# Adafruit_MatrixPortal_M4.net
KiCad netlist of a schematic drawn in EAGLE
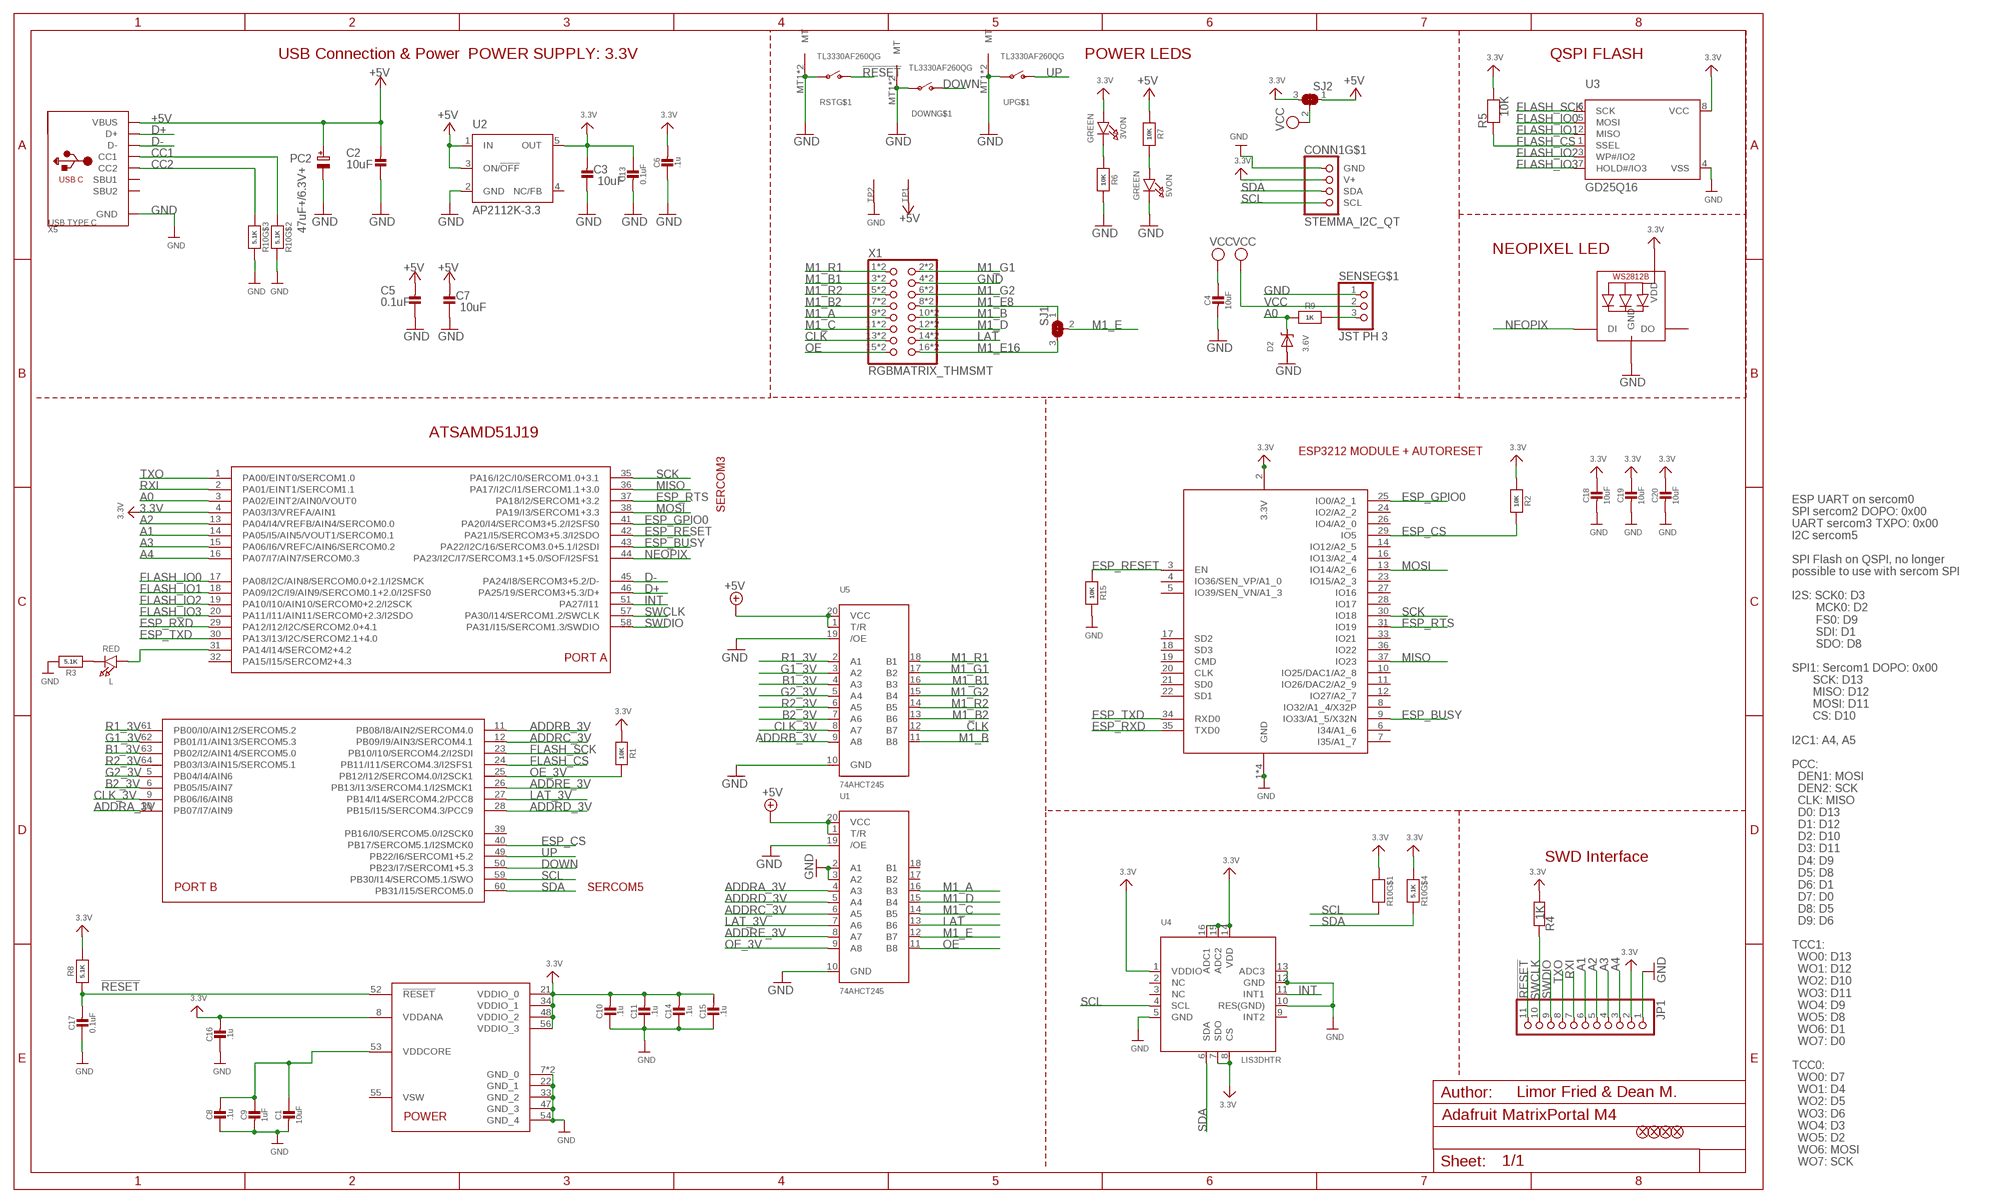
[diagram p0: schematic, sheet 1]

(export (version "E")
  (design (tool "Eeschema 10.0.6"))
  (components
    (comp (ref "3VON")
      (value "GREEN")
      (footprint "eagle-import:CHIPLED_0805_NOOUTLINE")
      (libsource (lib "eagle-import") (part "LED0805_NOOUTLINE"))
    )
    (comp (ref "5VON")
      (value "GREEN")
      (footprint "eagle-import:CHIPLED_0805_NOOUTLINE")
      (libsource (lib "eagle-import") (part "LED0805_NOOUTLINE"))
    )
    (comp (ref "C1")
      (value "10uF")
      (footprint "eagle-import:0805-NO")
      (libsource (lib "eagle-import") (part "CAP_CERAMIC0805-NOOUTLINE"))
    )
    (comp (ref "C2")
      (value "10uF")
      (footprint "eagle-import:0805-NO")
      (libsource (lib "eagle-import") (part "CAP_CERAMIC0805-NOOUTLINE"))
    )
    (comp (ref "C3")
      (value "10uF")
      (footprint "eagle-import:0805-NO")
      (libsource (lib "eagle-import") (part "CAP_CERAMIC0805-NOOUTLINE"))
    )
    (comp (ref "C4")
      (value "10uF")
      (footprint "eagle-import:0805-NO")
      (libsource (lib "eagle-import") (part "CAP_CERAMIC0805-NOOUTLINE"))
    )
    (comp (ref "C5")
      (value "0.1uF")
      (footprint "eagle-import:0603-NO")
      (libsource (lib "eagle-import") (part "CAP_CERAMIC0603_NO"))
    )
    (comp (ref "C6")
      (value ".1u")
      (footprint "eagle-import:0603-NO")
      (libsource (lib "eagle-import") (part "CAP_CERAMIC0603_NO"))
    )
    (comp (ref "C7")
      (value "10uF")
      (footprint "eagle-import:0805-NO")
      (libsource (lib "eagle-import") (part "CAP_CERAMIC0805-NOOUTLINE"))
    )
    (comp (ref "C8")
      (value ".1u")
      (footprint "eagle-import:0603-NO")
      (libsource (lib "eagle-import") (part "CAP_CERAMIC0603_NO"))
    )
    (comp (ref "C9")
      (value "1uF")
      (footprint "eagle-import:0603-NO")
      (libsource (lib "eagle-import") (part "CAP_CERAMIC0603_NO"))
    )
    (comp (ref "C10")
      (value ".1u")
      (footprint "eagle-import:0603-NO")
      (libsource (lib "eagle-import") (part "CAP_CERAMIC0603_NO"))
    )
    (comp (ref "C11")
      (value ".1u")
      (footprint "eagle-import:0603-NO")
      (libsource (lib "eagle-import") (part "CAP_CERAMIC0603_NO"))
    )
    (comp (ref "C13")
      (value "0.1uF")
      (footprint "eagle-import:0603-NO")
      (libsource (lib "eagle-import") (part "CAP_CERAMIC0603_NO"))
    )
    (comp (ref "C14")
      (value ".1u")
      (footprint "eagle-import:0603-NO")
      (libsource (lib "eagle-import") (part "CAP_CERAMIC0603_NO"))
    )
    (comp (ref "C15")
      (value ".1u")
      (footprint "eagle-import:0603-NO")
      (libsource (lib "eagle-import") (part "CAP_CERAMIC0603_NO"))
    )
    (comp (ref "C16")
      (value ".1u")
      (footprint "eagle-import:0603-NO")
      (libsource (lib "eagle-import") (part "CAP_CERAMIC0603_NO"))
    )
    (comp (ref "C17")
      (value "0.1uF")
      (footprint "eagle-import:0603-NO")
      (libsource (lib "eagle-import") (part "CAP_CERAMIC0603_NO"))
    )
    (comp (ref "C18")
      (value "10uF")
      (footprint "eagle-import:0805-NO")
      (libsource (lib "eagle-import") (part "CAP_CERAMIC0805-NOOUTLINE"))
    )
    (comp (ref "C19")
      (value "10uF")
      (footprint "eagle-import:0805-NO")
      (libsource (lib "eagle-import") (part "CAP_CERAMIC0805-NOOUTLINE"))
    )
    (comp (ref "C20")
      (value "10uF")
      (footprint "eagle-import:0805-NO")
      (libsource (lib "eagle-import") (part "CAP_CERAMIC0805-NOOUTLINE"))
    )
    (comp (ref "CONN1")
      (value "STEMMA_I2C_QT")
      (footprint "eagle-import:JST_SH4")
      (libsource (lib "eagle-import") (part "STEMMA_I2C_QT"))
    )
    (comp (ref "D2")
      (value "3.6V")
      (footprint "eagle-import:SOD-323")
      (libsource (lib "eagle-import") (part "DIODE-ZENERSOD323"))
    )
    (comp (ref "DOWN")
      (value "TL3330AF260QG")
      (footprint "eagle-import:SPST_TACTILE_RA")
      (libsource (lib "eagle-import") (part "SWITCH_SPST_TACT_RA"))
    )
    (comp (ref "FID1")
      (value "FIDUCIAL_1MM")
      (footprint "eagle-import:FIDUCIAL_1MM")
      (libsource (lib "eagle-import") (part "FIDUCIAL_1MM"))
    )
    (comp (ref "FID2")
      (value "FIDUCIAL_1MM")
      (footprint "eagle-import:FIDUCIAL_1MM")
      (libsource (lib "eagle-import") (part "FIDUCIAL_1MM"))
    )
    (comp (ref "FID3")
      (value "FIDUCIAL_1MM")
      (footprint "eagle-import:FIDUCIAL_1MM")
      (libsource (lib "eagle-import") (part "FIDUCIAL_1MM"))
    )
    (comp (ref "FID4")
      (value "FIDUCIAL_1MM")
      (footprint "eagle-import:FIDUCIAL_1MM")
      (libsource (lib "eagle-import") (part "FIDUCIAL_1MM"))
    )
    (comp (ref "JP1")
      (value "HEADER-1X11")
      (footprint "eagle-import:1X11_ROUND")
      (libsource (lib "eagle-import") (part "HEADER-1X11"))
    )
    (comp (ref "L")
      (value "RED")
      (footprint "eagle-import:CHIPLED_0603_NOOUTLINE")
      (libsource (lib "eagle-import") (part "LED0603_NOOUTLINE"))
    )
    (comp (ref "LED1")
      (value "WS2812B3535")
      (footprint "eagle-import:LED3535")
      (libsource (lib "eagle-import") (part "WS2812B3535"))
    )
    (comp (ref "PC2")
      (value "47uF+/6.3V+")
      (footprint "eagle-import:PANASONIC_D")
      (libsource (lib "eagle-import") (part "CAP_ELECTROLYTICPANASONIC_D"))
    )
    (comp (ref "R1")
      (value "10K")
      (footprint "eagle-import:0603-NO")
      (libsource (lib "eagle-import") (part "RESISTOR_0603_NOOUT"))
    )
    (comp (ref "R2")
      (value "10K")
      (footprint "eagle-import:0603-NO")
      (libsource (lib "eagle-import") (part "RESISTOR_0603_NOOUT"))
    )
    (comp (ref "R3")
      (value "5.1K")
      (footprint "eagle-import:0603-NO")
      (libsource (lib "eagle-import") (part "RESISTOR_0603_NOOUT"))
    )
    (comp (ref "R4")
      (value "1K")
      (footprint "eagle-import:0603-NO")
      (libsource (lib "eagle-import") (part "RESISTOR_0603_NOOUT"))
    )
    (comp (ref "R5")
      (value "10K")
      (footprint "eagle-import:0603-NO")
      (libsource (lib "eagle-import") (part "RESISTOR_0603_NOOUT"))
    )
    (comp (ref "R6")
      (value "10K")
      (footprint "eagle-import:0603-NO")
      (libsource (lib "eagle-import") (part "RESISTOR_0603_NOOUT"))
    )
    (comp (ref "R7")
      (value "10K")
      (footprint "eagle-import:0603-NO")
      (libsource (lib "eagle-import") (part "RESISTOR_0603_NOOUT"))
    )
    (comp (ref "R8")
      (value "5.1K")
      (footprint "eagle-import:0603-NO")
      (libsource (lib "eagle-import") (part "RESISTOR_0603_NOOUT"))
    )
    (comp (ref "R9")
      (value "1K")
      (footprint "eagle-import:0603-NO")
      (libsource (lib "eagle-import") (part "RESISTOR_0603_NOOUT"))
    )
    (comp (ref "R10")
      (value "5.1K")
      (footprint "eagle-import:RESPACK_4X0603")
      (libsource (lib "eagle-import") (part "RESISTOR_4PACK"))
    )
    (comp (ref "R15")
      (value "10K")
      (footprint "eagle-import:0603-NO")
      (libsource (lib "eagle-import") (part "RESISTOR_0603_NOOUT"))
    )
    (comp (ref "RST")
      (value "TL3330AF260QG")
      (footprint "eagle-import:SPST_TACTILE_RA")
      (libsource (lib "eagle-import") (part "SWITCH_SPST_TACT_RA"))
    )
    (comp (ref "SENSE")
      (value "JST PH 3")
      (footprint "eagle-import:JSTPH3")
      (libsource (lib "eagle-import") (part "CON_JST_PH_3PIN"))
    )
    (comp (ref "SJ1")
      (value "SOLDERJUMPER_2WAY")
      (footprint "eagle-import:SOLDERJUMPER_2WAY_OPEN_NOPASTE")
      (libsource (lib "eagle-import") (part "SOLDERJUMPER_2WAY"))
    )
    (comp (ref "SJ2")
      (value "SOLDERJUMPER_2WAY")
      (footprint "eagle-import:SOLDERJUMPER_2WAY_OPEN_NOPASTE")
      (libsource (lib "eagle-import") (part "SOLDERJUMPER_2WAY"))
    )
    (comp (ref "TP1")
      (value "SEWTAP_SMTNUTM3")
      (footprint "eagle-import:SMT_NUT_3MM")
      (libsource (lib "eagle-import") (part "SEWTAP_SMTNUTM3"))
    )
    (comp (ref "TP2")
      (value "SEWTAP_SMTNUTM3")
      (footprint "eagle-import:SMT_NUT_3MM")
      (libsource (lib "eagle-import") (part "SEWTAP_SMTNUTM3"))
    )
    (comp (ref "U$1")
      (value "ATSAMD51J19")
      (footprint "eagle-import:PQFN64-1")
      (libsource (lib "eagle-import") (part "ATSAMD51J"))
    )
    (comp (ref "U1")
      (value "74AHCT245")
      (footprint "eagle-import:TSSOP20")
      (libsource (lib "eagle-import") (part "74LCX245"))
    )
    (comp (ref "U2")
      (value "AP2112K-3.3")
      (footprint "eagle-import:SOT23-DBV")
      (libsource (lib "eagle-import") (part "LP2985-XXDBVR33"))
    )
    (comp (ref "U3")
      (value "GD25Q16")
      (footprint "eagle-import:SOIC8_208MIL")
      (libsource (lib "eagle-import") (part "SPIFLASH_8PIN208MIL"))
    )
    (comp (ref "U4")
      (value "LIS3DHTR")
      (footprint "eagle-import:LGA16_3X3MM")
      (libsource (lib "eagle-import") (part "ACCEL_LIS3DHTR"))
    )
    (comp (ref "U5")
      (value "74AHCT245")
      (footprint "eagle-import:TSSOP20")
      (libsource (lib "eagle-import") (part "74LCX245"))
    )
    (comp (ref "UP")
      (value "TL3330AF260QG")
      (footprint "eagle-import:SPST_TACTILE_RA")
      (libsource (lib "eagle-import") (part "SWITCH_SPST_TACT_RA"))
    )
    (comp (ref "X1")
      (value "RGBMATRIX_THMSMT")
      (footprint "eagle-import:2X08_SMTTHM_RGBMATRIX")
      (libsource (lib "eagle-import") (part "RGBMATRIX_THMSMT"))
    )
    (comp (ref "X5")
      (value "USB TYPE C")
      (footprint "eagle-import:USB_C_CUSB31-CFM2AX-01-X")
      (libsource (lib "eagle-import") (part "USB_C"))
    )
    (comp (ref "X6")
      (value "ESP32_WROOM32")
      (footprint "eagle-import:WROOM32")
      (libsource (lib "eagle-import") (part "ESP32_WROOM32"))
    )
  )
  (nets
    (net (code "1") (name "+5V") (class "Default")
      (node (ref "C2") (pin "2") (pinfunction "2_2") (pintype "passive"))
      (node (ref "C5") (pin "2") (pinfunction "2_2") (pintype "passive"))
      (node (ref "C7") (pin "2") (pinfunction "2_2") (pintype "passive"))
      (node (ref "PC2") (pin "+") (pinfunction "+_+") (pintype "passive"))
      (node (ref "R7") (pin "1") (pinfunction "1_1") (pintype "passive"))
      (node (ref "SJ2") (pin "1") (pinfunction "1_1") (pintype "passive"))
      (node (ref "TP1") (pin "P$1") (pinfunction "SEW_P$1") (pintype "bidirectional"))
      (node (ref "U1") (pin "1") (pinfunction "T/R_1") (pintype "bidirectional"))
      (node (ref "U1") (pin "20") (pinfunction "VCC_20") (pintype "bidirectional"))
      (node (ref "U2") (pin "1") (pinfunction "IN_1") (pintype "input"))
      (node (ref "U2") (pin "3") (pinfunction "ON/~{OFF}_3") (pintype "input"))
      (node (ref "U5") (pin "1") (pinfunction "T/R_1") (pintype "bidirectional"))
      (node (ref "U5") (pin "20") (pinfunction "VCC_20") (pintype "bidirectional"))
      (node (ref "X5") (pin "A4B9") (pinfunction "VBUS_A4B9") (pintype "power_in"))
      (node (ref "X5") (pin "B4A9") (pinfunction "VBUS_B4A9") (pintype "power_in"))
    )
    (net (code "2") (name "/A0") (class "Default")
      (node (ref "D2") (pin "C") (pinfunction "C_C") (pintype "passive"))
      (node (ref "R9") (pin "2") (pinfunction "2_2") (pintype "passive"))
      (node (ref "U$1") (pin "3") (pinfunction "PA02/EINT2/AIN0/VOUT0_3") (pintype "bidirectional"))
    )
    (net (code "3") (name "/A1") (class "Default")
      (node (ref "JP1") (pin "6") (pinfunction "6_6") (pintype "passive"))
      (node (ref "U$1") (pin "14") (pinfunction "PA05/I5/AIN5/VOUT1/SERCOM0.1_14") (pintype "bidirectional"))
    )
    (net (code "4") (name "/A2") (class "Default")
      (node (ref "JP1") (pin "5") (pinfunction "5_5") (pintype "passive"))
      (node (ref "U$1") (pin "13") (pinfunction "PA04/I4/VREFB/AIN4/SERCOM0.0_13") (pintype "bidirectional"))
    )
    (net (code "5") (name "/A3") (class "Default")
      (node (ref "JP1") (pin "4") (pinfunction "4_4") (pintype "passive"))
      (node (ref "U$1") (pin "15") (pinfunction "PA06/I6/VREFC/AIN6/SERCOM0.2_15") (pintype "bidirectional"))
    )
    (net (code "6") (name "/A4") (class "Default")
      (node (ref "JP1") (pin "3") (pinfunction "3_3") (pintype "passive"))
      (node (ref "U$1") (pin "16") (pinfunction "PA07/I7/AIN7/SERCOM0.3_16") (pintype "bidirectional"))
    )
    (net (code "7") (name "/ADDRA_3V") (class "Default")
      (node (ref "U$1") (pin "10") (pinfunction "PB07/I7/AIN9_10") (pintype "bidirectional"))
      (node (ref "U1") (pin "4") (pinfunction "A3_4") (pintype "bidirectional"))
    )
    (net (code "8") (name "/ADDRB_3V") (class "Default")
      (node (ref "U$1") (pin "11") (pinfunction "PB08/I8/AIN2/SERCOM4.0_11") (pintype "bidirectional"))
      (node (ref "U5") (pin "9") (pinfunction "A8_9") (pintype "bidirectional"))
    )
    (net (code "9") (name "/ADDRC_3V") (class "Default")
      (node (ref "U$1") (pin "12") (pinfunction "PB09/I9/AIN3/SERCOM4.1_12") (pintype "bidirectional"))
      (node (ref "U1") (pin "6") (pinfunction "A5_6") (pintype "bidirectional"))
    )
    (net (code "10") (name "/ADDRD_3V") (class "Default")
      (node (ref "U$1") (pin "28") (pinfunction "PB15/I15/SERCOM4.3/PCC9_28") (pintype "bidirectional"))
      (node (ref "U1") (pin "5") (pinfunction "A4_5") (pintype "bidirectional"))
    )
    (net (code "11") (name "/ADDRE_3V") (class "Default")
      (node (ref "U$1") (pin "26") (pinfunction "PB13/I13/SERCOM4.1/I2SMCK1_26") (pintype "bidirectional"))
      (node (ref "U1") (pin "8") (pinfunction "A7_8") (pintype "bidirectional"))
    )
    (net (code "12") (name "/B1_3V") (class "Default")
      (node (ref "U$1") (pin "63") (pinfunction "PB02/I2/AIN14/SERCOM5.0_63") (pintype "bidirectional"))
      (node (ref "U5") (pin "4") (pinfunction "A3_4") (pintype "bidirectional"))
    )
    (net (code "13") (name "/B2_3V") (class "Default")
      (node (ref "U$1") (pin "6") (pinfunction "PB05/I5/AIN7_6") (pintype "bidirectional"))
      (node (ref "U5") (pin "7") (pinfunction "A6_7") (pintype "bidirectional"))
    )
    (net (code "14") (name "/CC1") (class "Default")
      (node (ref "R10") (pin "2") (pinfunction "1_2") (pintype "passive"))
      (node (ref "X5") (pin "A5") (pinfunction "CC1_A5") (pintype "bidirectional"))
    )
    (net (code "15") (name "/CC2") (class "Default")
      (node (ref "R10") (pin "3") (pinfunction "1_3") (pintype "passive"))
      (node (ref "X5") (pin "B5") (pinfunction "CC2_B5") (pintype "bidirectional"))
    )
    (net (code "16") (name "/CLK") (class "Default")
      (node (ref "U5") (pin "12") (pinfunction "B7_12") (pintype "bidirectional"))
      (node (ref "X1") (pin "13") (pinfunction "13_13") (pintype "passive"))
      (node (ref "X1") (pin "13S") (pinfunction "13_13S") (pintype "passive"))
    )
    (net (code "17") (name "/CLK_3V") (class "Default")
      (node (ref "U$1") (pin "9") (pinfunction "PB06/I6/AIN8_9") (pintype "bidirectional"))
      (node (ref "U5") (pin "8") (pinfunction "A7_8") (pintype "bidirectional"))
    )
    (net (code "18") (name "/D+") (class "Default")
      (node (ref "U$1") (pin "46") (pinfunction "PA25/19/SERCOM3+5.3/D+_46") (pintype "bidirectional"))
      (node (ref "X5") (pin "A6") (pinfunction "D+_A6") (pintype "bidirectional"))
      (node (ref "X5") (pin "B6") (pinfunction "D+_B6") (pintype "bidirectional"))
    )
    (net (code "19") (name "/D-") (class "Default")
      (node (ref "U$1") (pin "45") (pinfunction "PA24/I8/SERCOM3+5.2/D-_45") (pintype "bidirectional"))
      (node (ref "X5") (pin "A7") (pinfunction "D-_A7") (pintype "bidirectional"))
      (node (ref "X5") (pin "B7") (pinfunction "D-_B7") (pintype "bidirectional"))
    )
    (net (code "20") (name "/DOWN") (class "Default")
      (node (ref "DOWN") (pin "2") (pinfunction "S_2") (pintype "passive"))
      (node (ref "U$1") (pin "50") (pinfunction "PB23/I7/SERCOM1+5.3_50") (pintype "bidirectional"))
    )
    (net (code "21") (name "/ESP_BUSY") (class "Default")
      (node (ref "U$1") (pin "43") (pinfunction "PA22/I2C/16/SERCOM3.0+5.1/I2SDI_43") (pintype "bidirectional"))
      (node (ref "X6") (pin "9") (pinfunction "IO33/A1_5/X32N_9") (pintype "bidirectional"))
    )
    (net (code "22") (name "/ESP_CS") (class "Default")
      (node (ref "R2") (pin "2") (pinfunction "2_2") (pintype "passive"))
      (node (ref "U$1") (pin "40") (pinfunction "PB17/SERCOM5.1/I2SMCK0_40") (pintype "bidirectional"))
      (node (ref "X6") (pin "29") (pinfunction "IO5_29") (pintype "bidirectional"))
    )
    (net (code "23") (name "/ESP_GPIO0") (class "Default")
      (node (ref "U$1") (pin "41") (pinfunction "PA20/I4/SERCOM3+5.2/I2SFS0_41") (pintype "bidirectional"))
      (node (ref "X6") (pin "25") (pinfunction "IO0/A2_1_25") (pintype "bidirectional"))
    )
    (net (code "24") (name "/ESP_RESET") (class "Default")
      (node (ref "R15") (pin "1") (pinfunction "1_1") (pintype "passive"))
      (node (ref "U$1") (pin "42") (pinfunction "PA21/I5/SERCOM3+5.3/I2SDO_42") (pintype "bidirectional"))
      (node (ref "X6") (pin "3") (pinfunction "EN_3") (pintype "input"))
    )
    (net (code "25") (name "/ESP_RTS") (class "Default")
      (node (ref "U$1") (pin "37") (pinfunction "PA18/I2/SERCOM1+3.2_37") (pintype "bidirectional"))
      (node (ref "X6") (pin "31") (pinfunction "IO19_31") (pintype "bidirectional"))
    )
    (net (code "26") (name "/ESP_RXD") (class "Default")
      (node (ref "U$1") (pin "29") (pinfunction "PA12/I12/I2C/SERCOM2.0+4.1_29") (pintype "bidirectional"))
      (node (ref "X6") (pin "35") (pinfunction "TXD0_35") (pintype "output"))
    )
    (net (code "27") (name "/ESP_TXD") (class "Default")
      (node (ref "U$1") (pin "30") (pinfunction "PA13/I13/I2C/SERCOM2.1+4.0_30") (pintype "bidirectional"))
      (node (ref "X6") (pin "34") (pinfunction "RXD0_34") (pintype "input"))
    )
    (net (code "28") (name "/FLASH_CS") (class "Default")
      (node (ref "R5") (pin "1") (pinfunction "1_1") (pintype "passive"))
      (node (ref "U$1") (pin "24") (pinfunction "PB11/I11/SERCOM4.3/I2SFS1_24") (pintype "bidirectional"))
      (node (ref "U3") (pin "1") (pinfunction "SSEL_1") (pintype "bidirectional"))
    )
    (net (code "29") (name "/FLASH_IO0") (class "Default")
      (node (ref "U$1") (pin "17") (pinfunction "PA08/I2C/AIN8/SERCOM0.0+2.1/I2SMCK_17") (pintype "bidirectional"))
      (node (ref "U3") (pin "5") (pinfunction "MOSI_5") (pintype "bidirectional"))
    )
    (net (code "30") (name "/FLASH_IO1") (class "Default")
      (node (ref "U$1") (pin "18") (pinfunction "PA09/I2C/I9/AIN9/SERCOM0.1+2.0/I2SFS0_18") (pintype "bidirectional"))
      (node (ref "U3") (pin "2") (pinfunction "MISO_2") (pintype "bidirectional"))
    )
    (net (code "31") (name "/FLASH_IO2") (class "Default")
      (node (ref "U$1") (pin "19") (pinfunction "PA10/I10/AIN10/SERCOM0+2.2/I2SCK_19") (pintype "bidirectional"))
      (node (ref "U3") (pin "3") (pinfunction "WP#/IO2_3") (pintype "bidirectional"))
    )
    (net (code "32") (name "/FLASH_IO3") (class "Default")
      (node (ref "U$1") (pin "20") (pinfunction "PA11/I11/AIN11/SERCOM0+2.3/I2SDO_20") (pintype "bidirectional"))
      (node (ref "U3") (pin "7") (pinfunction "HOLD#/IO3_7") (pintype "bidirectional"))
    )
    (net (code "33") (name "/FLASH_SCK") (class "Default")
      (node (ref "U$1") (pin "23") (pinfunction "PB10/I10/SERCOM4.2/I2SDI_23") (pintype "bidirectional"))
      (node (ref "U3") (pin "6") (pinfunction "SCK_6") (pintype "bidirectional"))
    )
    (net (code "34") (name "/G1_3V") (class "Default")
      (node (ref "U$1") (pin "62") (pinfunction "PB01/I1/AIN13/SERCOM5.3_62") (pintype "bidirectional"))
      (node (ref "U5") (pin "3") (pinfunction "A2_3") (pintype "bidirectional"))
    )
    (net (code "35") (name "/G2_3V") (class "Default")
      (node (ref "U$1") (pin "5") (pinfunction "PB04/I4/AIN6_5") (pintype "bidirectional"))
      (node (ref "U5") (pin "5") (pinfunction "A4_5") (pintype "bidirectional"))
    )
    (net (code "36") (name "/INT") (class "Default")
      (node (ref "U$1") (pin "51") (pinfunction "PA27/I11_51") (pintype "bidirectional"))
      (node (ref "U4") (pin "11") (pinfunction "INT1_11") (pintype "output"))
    )
    (net (code "37") (name "/LAT") (class "Default")
      (node (ref "U1") (pin "13") (pinfunction "B6_13") (pintype "bidirectional"))
      (node (ref "X1") (pin "14") (pinfunction "14_14") (pintype "passive"))
      (node (ref "X1") (pin "14S") (pinfunction "14_14S") (pintype "passive"))
    )
    (net (code "38") (name "/LAT_3V") (class "Default")
      (node (ref "U$1") (pin "27") (pinfunction "PB14/I14/SERCOM4.2/PCC8_27") (pintype "bidirectional"))
      (node (ref "U1") (pin "7") (pinfunction "A6_7") (pintype "bidirectional"))
    )
    (net (code "39") (name "/M1_A") (class "Default")
      (node (ref "U1") (pin "16") (pinfunction "B3_16") (pintype "bidirectional"))
      (node (ref "X1") (pin "9") (pinfunction "9_9") (pintype "passive"))
      (node (ref "X1") (pin "9S") (pinfunction "9_9S") (pintype "passive"))
    )
    (net (code "40") (name "/M1_B") (class "Default")
      (node (ref "U5") (pin "11") (pinfunction "B8_11") (pintype "bidirectional"))
      (node (ref "X1") (pin "10") (pinfunction "10_10") (pintype "passive"))
      (node (ref "X1") (pin "10S") (pinfunction "10_10S") (pintype "passive"))
    )
    (net (code "41") (name "/M1_B1") (class "Default")
      (node (ref "U5") (pin "16") (pinfunction "B3_16") (pintype "bidirectional"))
      (node (ref "X1") (pin "3") (pinfunction "3_3") (pintype "passive"))
      (node (ref "X1") (pin "3S") (pinfunction "3_3S") (pintype "passive"))
    )
    (net (code "42") (name "/M1_B2") (class "Default")
      (node (ref "U5") (pin "13") (pinfunction "B6_13") (pintype "bidirectional"))
      (node (ref "X1") (pin "7") (pinfunction "7_7") (pintype "passive"))
      (node (ref "X1") (pin "7S") (pinfunction "7_7S") (pintype "passive"))
    )
    (net (code "43") (name "/M1_C") (class "Default")
      (node (ref "U1") (pin "14") (pinfunction "B5_14") (pintype "bidirectional"))
      (node (ref "X1") (pin "11") (pinfunction "11_11") (pintype "passive"))
      (node (ref "X1") (pin "11S") (pinfunction "11_11S") (pintype "passive"))
    )
    (net (code "44") (name "/M1_D") (class "Default")
      (node (ref "U1") (pin "15") (pinfunction "B4_15") (pintype "bidirectional"))
      (node (ref "X1") (pin "12") (pinfunction "12_12") (pintype "passive"))
      (node (ref "X1") (pin "12S") (pinfunction "12_12S") (pintype "passive"))
    )
    (net (code "45") (name "/M1_E") (class "Default")
      (node (ref "SJ1") (pin "2") (pinfunction "2_2") (pintype "passive"))
      (node (ref "U1") (pin "12") (pinfunction "B7_12") (pintype "bidirectional"))
    )
    (net (code "46") (name "/M1_E8") (class "Default")
      (node (ref "SJ1") (pin "1") (pinfunction "1_1") (pintype "passive"))
      (node (ref "X1") (pin "8") (pinfunction "8_8") (pintype "passive"))
      (node (ref "X1") (pin "8S") (pinfunction "8_8S") (pintype "passive"))
    )
    (net (code "47") (name "/M1_E16") (class "Default")
      (node (ref "SJ1") (pin "3") (pinfunction "3_3") (pintype "passive"))
      (node (ref "X1") (pin "16") (pinfunction "16_16") (pintype "passive"))
      (node (ref "X1") (pin "16S") (pinfunction "16_16S") (pintype "passive"))
    )
    (net (code "48") (name "/M1_G1") (class "Default")
      (node (ref "U5") (pin "17") (pinfunction "B2_17") (pintype "bidirectional"))
      (node (ref "X1") (pin "2") (pinfunction "2_2") (pintype "passive"))
      (node (ref "X1") (pin "2S") (pinfunction "2_2S") (pintype "passive"))
    )
    (net (code "49") (name "/M1_G2") (class "Default")
      (node (ref "U5") (pin "15") (pinfunction "B4_15") (pintype "bidirectional"))
      (node (ref "X1") (pin "6") (pinfunction "6_6") (pintype "passive"))
      (node (ref "X1") (pin "6S") (pinfunction "6_6S") (pintype "passive"))
    )
    (net (code "50") (name "/M1_R1") (class "Default")
      (node (ref "U5") (pin "18") (pinfunction "B1_18") (pintype "bidirectional"))
      (node (ref "X1") (pin "1") (pinfunction "1_1") (pintype "passive"))
      (node (ref "X1") (pin "1S") (pinfunction "1_1S") (pintype "passive"))
    )
    (net (code "51") (name "/M1_R2") (class "Default")
      (node (ref "U5") (pin "14") (pinfunction "B5_14") (pintype "bidirectional"))
      (node (ref "X1") (pin "5") (pinfunction "5_5") (pintype "passive"))
      (node (ref "X1") (pin "5S") (pinfunction "5_5S") (pintype "passive"))
    )
    (net (code "52") (name "/MISO") (class "Default")
      (node (ref "U$1") (pin "36") (pinfunction "PA17/I2C/I1/SERCOM1.1+3.0_36") (pintype "bidirectional"))
      (node (ref "X6") (pin "37") (pinfunction "IO23_37") (pintype "bidirectional"))
    )
    (net (code "53") (name "/MOSI") (class "Default")
      (node (ref "U$1") (pin "38") (pinfunction "PA19/I3/SERCOM1+3.3_38") (pintype "bidirectional"))
      (node (ref "X6") (pin "13") (pinfunction "IO14/A2_6_13") (pintype "bidirectional"))
    )
    (net (code "54") (name "/NEOPIX") (class "Default")
      (node (ref "LED1") (pin "1") (pinfunction "DI_1") (pintype "input"))
      (node (ref "U$1") (pin "44") (pinfunction "PA23/I2C/I7/SERCOM3.1+5.0/SOF/I2SFS1_44") (pintype "bidirectional"))
    )
    (net (code "55") (name "/OE") (class "Default")
      (node (ref "U1") (pin "11") (pinfunction "B8_11") (pintype "bidirectional"))
      (node (ref "X1") (pin "15") (pinfunction "15_15") (pintype "passive"))
      (node (ref "X1") (pin "15S") (pinfunction "15_15S") (pintype "passive"))
    )
    (net (code "56") (name "/OE_3V") (class "Default")
      (node (ref "R1") (pin "2") (pinfunction "2_2") (pintype "passive"))
      (node (ref "U$1") (pin "25") (pinfunction "PB12/I12/SERCOM4.0/I2SCK1_25") (pintype "bidirectional"))
      (node (ref "U1") (pin "9") (pinfunction "A8_9") (pintype "bidirectional"))
    )
    (net (code "57") (name "/R1_3V") (class "Default")
      (node (ref "U$1") (pin "61") (pinfunction "PB00/I0/AIN12/SERCOM5.2_61") (pintype "bidirectional"))
      (node (ref "U5") (pin "2") (pinfunction "A1_2") (pintype "bidirectional"))
    )
    (net (code "58") (name "/R2_3V") (class "Default")
      (node (ref "U$1") (pin "64") (pinfunction "PB03/I3/AIN15/SERCOM5.1_64") (pintype "bidirectional"))
      (node (ref "U5") (pin "6") (pinfunction "A5_6") (pintype "bidirectional"))
    )
    (net (code "59") (name "/RXI") (class "Default")
      (node (ref "JP1") (pin "7") (pinfunction "7_7") (pintype "passive"))
      (node (ref "U$1") (pin "2") (pinfunction "PA01/EINT1/SERCOM1.1_2") (pintype "bidirectional"))
    )
    (net (code "60") (name "/SCK") (class "Default")
      (node (ref "U$1") (pin "35") (pinfunction "PA16/I2C/I0/SERCOM1.0+3.1_35") (pintype "bidirectional"))
      (node (ref "X6") (pin "30") (pinfunction "IO18_30") (pintype "bidirectional"))
    )
    (net (code "61") (name "/SCL") (class "Default")
      (node (ref "CONN1") (pin "4") (pinfunction "SCL_4") (pintype "passive"))
      (node (ref "R10") (pin "8") (pinfunction "2_8") (pintype "passive"))
      (node (ref "U$1") (pin "59") (pinfunction "PB30/I14/SERCOM5.1/SWO_59") (pintype "bidirectional"))
      (node (ref "U4") (pin "4") (pinfunction "SCL_4") (pintype "bidirectional"))
    )
    (net (code "62") (name "/SDA") (class "Default")
      (node (ref "CONN1") (pin "3") (pinfunction "SDA_3") (pintype "passive"))
      (node (ref "R10") (pin "5") (pinfunction "2_5") (pintype "passive"))
      (node (ref "U$1") (pin "60") (pinfunction "PB31/I15/SERCOM5.0_60") (pintype "bidirectional"))
      (node (ref "U4") (pin "6") (pinfunction "SDA_6") (pintype "bidirectional"))
    )
    (net (code "63") (name "/SWCLK") (class "Default")
      (node (ref "JP1") (pin "10") (pinfunction "10_10") (pintype "passive"))
      (node (ref "R4") (pin "1") (pinfunction "1_1") (pintype "passive"))
      (node (ref "U$1") (pin "57") (pinfunction "PA30/I14/SERCOM1.2/SWCLK_57") (pintype "bidirectional"))
    )
    (net (code "64") (name "/SWDIO") (class "Default")
      (node (ref "JP1") (pin "9") (pinfunction "9_9") (pintype "passive"))
      (node (ref "U$1") (pin "58") (pinfunction "PA31/I15/SERCOM1.3/SWDIO_58") (pintype "bidirectional"))
    )
    (net (code "65") (name "/TXO") (class "Default")
      (node (ref "JP1") (pin "8") (pinfunction "8_8") (pintype "passive"))
      (node (ref "U$1") (pin "1") (pinfunction "PA00/EINT0/SERCOM1.0_1") (pintype "bidirectional"))
    )
    (net (code "66") (name "/UP") (class "Default")
      (node (ref "U$1") (pin "49") (pinfunction "PB22/I6/SERCOM1+5.2_49") (pintype "bidirectional"))
      (node (ref "UP") (pin "2") (pinfunction "S_2") (pintype "passive"))
    )
    (net (code "67") (name "/~{RESET}") (class "Default")
      (node (ref "C17") (pin "2") (pinfunction "2_2") (pintype "passive"))
      (node (ref "JP1") (pin "11") (pinfunction "11_11") (pintype "passive"))
      (node (ref "R8") (pin "1") (pinfunction "1_1") (pintype "passive"))
      (node (ref "RST") (pin "2") (pinfunction "S_2") (pintype "passive"))
      (node (ref "U$1") (pin "52") (pinfunction "~{RESET}_52") (pintype "bidirectional"))
    )
    (net (code "68") (name "3.3V") (class "Default")
      (node (ref "3VON") (pin "A") (pinfunction "A_A") (pintype "passive"))
      (node (ref "C10") (pin "2") (pinfunction "2_2") (pintype "passive"))
      (node (ref "C11") (pin "2") (pinfunction "2_2") (pintype "passive"))
      (node (ref "C13") (pin "1") (pinfunction "1_1") (pintype "passive"))
      (node (ref "C14") (pin "2") (pinfunction "2_2") (pintype "passive"))
      (node (ref "C15") (pin "2") (pinfunction "2_2") (pintype "passive"))
      (node (ref "C16") (pin "2") (pinfunction "2_2") (pintype "passive"))
      (node (ref "C18") (pin "1") (pinfunction "1_1") (pintype "passive"))
      (node (ref "C19") (pin "1") (pinfunction "1_1") (pintype "passive"))
      (node (ref "C20") (pin "1") (pinfunction "1_1") (pintype "passive"))
      (node (ref "C3") (pin "2") (pinfunction "2_2") (pintype "passive"))
      (node (ref "C6") (pin "2") (pinfunction "2_2") (pintype "passive"))
      (node (ref "CONN1") (pin "2") (pinfunction "V+_2") (pintype "passive"))
      (node (ref "JP1") (pin "2") (pinfunction "2_2") (pintype "passive"))
      (node (ref "LED1") (pin "2") (pinfunction "VDD_2") (pintype "power_in"))
      (node (ref "R1") (pin "1") (pinfunction "1_1") (pintype "passive"))
      (node (ref "R10") (pin "1") (pinfunction "1_1") (pintype "passive"))
      (node (ref "R10") (pin "4") (pinfunction "1_4") (pintype "passive"))
      (node (ref "R2") (pin "1") (pinfunction "1_1") (pintype "passive"))
      (node (ref "R4") (pin "2") (pinfunction "2_2") (pintype "passive"))
      (node (ref "R5") (pin "2") (pinfunction "2_2") (pintype "passive"))
      (node (ref "R8") (pin "2") (pinfunction "2_2") (pintype "passive"))
      (node (ref "SJ2") (pin "3") (pinfunction "3_3") (pintype "passive"))
      (node (ref "U$1") (pin "21") (pinfunction "VDDIO_0_21") (pintype "bidirectional"))
      (node (ref "U$1") (pin "34") (pinfunction "VDDIO_1_34") (pintype "bidirectional"))
      (node (ref "U$1") (pin "4") (pinfunction "PA03/I3/VREFA/AIN1_4") (pintype "bidirectional"))
      (node (ref "U$1") (pin "48") (pinfunction "VDDIO_2_48") (pintype "bidirectional"))
      (node (ref "U$1") (pin "56") (pinfunction "VDDIO_3_56") (pintype "bidirectional"))
      (node (ref "U$1") (pin "8") (pinfunction "VDDANA_8") (pintype "bidirectional"))
      (node (ref "U2") (pin "5") (pinfunction "OUT_5") (pintype "passive"))
      (node (ref "U3") (pin "8") (pinfunction "VCC_8") (pintype "bidirectional"))
      (node (ref "U4") (pin "1") (pinfunction "VDDIO_1") (pintype "power_in"))
      (node (ref "U4") (pin "14") (pinfunction "VDD_14") (pintype "power_in"))
      (node (ref "U4") (pin "15") (pinfunction "ADC2_15") (pintype "input"))
      (node (ref "U4") (pin "16") (pinfunction "ADC1_16") (pintype "input"))
      (node (ref "U4") (pin "7") (pinfunction "SDO_7") (pintype "bidirectional"))
      (node (ref "U4") (pin "8") (pinfunction "CS_8") (pintype "input"))
      (node (ref "X6") (pin "2") (pinfunction "3.3V_2") (pintype "passive"))
    )
    (net (code "69") (name "GND") (class "Default")
      (node (ref "5VON") (pin "C") (pinfunction "C_C") (pintype "passive"))
      (node (ref "C1") (pin "2") (pinfunction "2_2") (pintype "passive"))
      (node (ref "C10") (pin "1") (pinfunction "1_1") (pintype "passive"))
      (node (ref "C11") (pin "1") (pinfunction "1_1") (pintype "passive"))
      (node (ref "C13") (pin "2") (pinfunction "2_2") (pintype "passive"))
      (node (ref "C14") (pin "1") (pinfunction "1_1") (pintype "passive"))
      (node (ref "C15") (pin "1") (pinfunction "1_1") (pintype "passive"))
      (node (ref "C16") (pin "1") (pinfunction "1_1") (pintype "passive"))
      (node (ref "C17") (pin "1") (pinfunction "1_1") (pintype "passive"))
      (node (ref "C18") (pin "2") (pinfunction "2_2") (pintype "passive"))
      (node (ref "C19") (pin "2") (pinfunction "2_2") (pintype "passive"))
      (node (ref "C2") (pin "1") (pinfunction "1_1") (pintype "passive"))
      (node (ref "C20") (pin "2") (pinfunction "2_2") (pintype "passive"))
      (node (ref "C3") (pin "1") (pinfunction "1_1") (pintype "passive"))
      (node (ref "C4") (pin "2") (pinfunction "2_2") (pintype "passive"))
      (node (ref "C5") (pin "1") (pinfunction "1_1") (pintype "passive"))
      (node (ref "C6") (pin "1") (pinfunction "1_1") (pintype "passive"))
      (node (ref "C7") (pin "1") (pinfunction "1_1") (pintype "passive"))
      (node (ref "C8") (pin "1") (pinfunction "1_1") (pintype "passive"))
      (node (ref "C9") (pin "2") (pinfunction "2_2") (pintype "passive"))
      (node (ref "CONN1") (pin "1") (pinfunction "GND_1") (pintype "passive"))
      (node (ref "D2") (pin "A") (pinfunction "A_A") (pintype "passive"))
      (node (ref "DOWN") (pin "1") (pinfunction "P_1") (pintype "passive"))
      (node (ref "DOWN") (pin "MT1") (pinfunction "MT_MT1") (pintype "bidirectional"))
      (node (ref "DOWN") (pin "MT2") (pinfunction "MT_MT2") (pintype "bidirectional"))
      (node (ref "JP1") (pin "1") (pinfunction "1_1") (pintype "passive"))
      (node (ref "LED1") (pin "4") (pinfunction "GND_4") (pintype "power_in"))
      (node (ref "PC2") (pin "-") (pinfunction "-_-") (pintype "passive"))
      (node (ref "R10") (pin "6") (pinfunction "2_6") (pintype "passive"))
      (node (ref "R10") (pin "7") (pinfunction "2_7") (pintype "passive"))
      (node (ref "R15") (pin "2") (pinfunction "2_2") (pintype "passive"))
      (node (ref "R3") (pin "2") (pinfunction "2_2") (pintype "passive"))
      (node (ref "R6") (pin "2") (pinfunction "2_2") (pintype "passive"))
      (node (ref "RST") (pin "1") (pinfunction "P_1") (pintype "passive"))
      (node (ref "RST") (pin "MT1") (pinfunction "MT_MT1") (pintype "bidirectional"))
      (node (ref "RST") (pin "MT2") (pinfunction "MT_MT2") (pintype "bidirectional"))
      (node (ref "SENSE") (pin "1") (pinfunction "1_1") (pintype "passive"))
      (node (ref "TP2") (pin "P$1") (pinfunction "SEW_P$1") (pintype "bidirectional"))
      (node (ref "U$1") (pin "22") (pinfunction "GND_1_22") (pintype "bidirectional"))
      (node (ref "U$1") (pin "33") (pinfunction "GND_2_33") (pintype "bidirectional"))
      (node (ref "U$1") (pin "47") (pinfunction "GND_3_47") (pintype "bidirectional"))
      (node (ref "U$1") (pin "54") (pinfunction "GND_4_54") (pintype "bidirectional"))
      (node (ref "U$1") (pin "7") (pinfunction "GND_0_7") (pintype "bidirectional"))
      (node (ref "U$1") (pin "EXP") (pinfunction "GND_0_EXP") (pintype "bidirectional"))
      (node (ref "U1") (pin "10") (pinfunction "GND_10") (pintype "bidirectional"))
      (node (ref "U1") (pin "19") (pinfunction "/OE_19") (pintype "bidirectional"))
      (node (ref "U1") (pin "2") (pinfunction "A1_2") (pintype "bidirectional"))
      (node (ref "U1") (pin "3") (pinfunction "A2_3") (pintype "bidirectional"))
      (node (ref "U2") (pin "2") (pinfunction "GND_2") (pintype "power_in"))
      (node (ref "U3") (pin "4") (pinfunction "VSS_4") (pintype "bidirectional"))
      (node (ref "U4") (pin "10") (pinfunction "RES(GND)_10") (pintype "bidirectional"))
      (node (ref "U4") (pin "12") (pinfunction "GND_12") (pintype "power_in"))
      (node (ref "U4") (pin "13") (pinfunction "ADC3_13") (pintype "input"))
      (node (ref "U4") (pin "5") (pinfunction "GND_5") (pintype "power_in"))
      (node (ref "U5") (pin "10") (pinfunction "GND_10") (pintype "bidirectional"))
      (node (ref "U5") (pin "19") (pinfunction "/OE_19") (pintype "bidirectional"))
      (node (ref "UP") (pin "1") (pinfunction "P_1") (pintype "passive"))
      (node (ref "UP") (pin "MT1") (pinfunction "MT_MT1") (pintype "bidirectional"))
      (node (ref "UP") (pin "MT2") (pinfunction "MT_MT2") (pintype "bidirectional"))
      (node (ref "X1") (pin "4") (pinfunction "4_4") (pintype "passive"))
      (node (ref "X1") (pin "4S") (pinfunction "4_4S") (pintype "passive"))
      (node (ref "X5") (pin "A1B12") (pinfunction "GND_A1B12") (pintype "power_in"))
      (node (ref "X5") (pin "B1A12") (pinfunction "GND_B1A12") (pintype "power_in"))
      (node (ref "X6") (pin "1") (pinfunction "GND_1") (pintype "passive"))
      (node (ref "X6") (pin "15") (pinfunction "GND_15") (pintype "passive"))
      (node (ref "X6") (pin "38") (pinfunction "GND_38") (pintype "passive"))
      (node (ref "X6") (pin "P$1") (pinfunction "GND_P$1") (pintype "passive"))
    )
    (net (code "70") (name "Net-(3VON-PadC)") (class "Default")
      (node (ref "3VON") (pin "C") (pinfunction "C_C") (pintype "passive"))
      (node (ref "R6") (pin "1") (pinfunction "1_1") (pintype "passive"))
    )
    (net (code "71") (name "Net-(5VON-PadA)") (class "Default")
      (node (ref "5VON") (pin "A") (pinfunction "A_A") (pintype "passive"))
      (node (ref "R7") (pin "2") (pinfunction "2_2") (pintype "passive"))
    )
    (net (code "72") (name "Net-(L-PadC)") (class "Default")
      (node (ref "L") (pin "C") (pinfunction "C_C") (pintype "passive"))
      (node (ref "R3") (pin "1") (pinfunction "1_1") (pintype "passive"))
    )
    (net (code "73") (name "Net-(R9-Pad1)") (class "Default")
      (node (ref "R9") (pin "1") (pinfunction "1_1") (pintype "passive"))
      (node (ref "SENSE") (pin "3") (pinfunction "3_3") (pintype "passive"))
    )
    (net (code "74") (name "Net-(U$1A-PA14{slash}I14{slash}SERCOM2+4.2)") (class "Default")
      (node (ref "L") (pin "A") (pinfunction "A_A") (pintype "passive"))
      (node (ref "U$1") (pin "31") (pinfunction "PA14/I14/SERCOM2+4.2_31") (pintype "bidirectional"))
    )
    (net (code "75") (name "Net-(U$1C-VDDCORE)") (class "Default")
      (node (ref "C1") (pin "1") (pinfunction "1_1") (pintype "passive"))
      (node (ref "C8") (pin "2") (pinfunction "2_2") (pintype "passive"))
      (node (ref "C9") (pin "1") (pinfunction "1_1") (pintype "passive"))
      (node (ref "U$1") (pin "53") (pinfunction "VDDCORE_53") (pintype "bidirectional"))
    )
    (net (code "76") (name "VCC") (class "Default")
      (node (ref "C4") (pin "1") (pinfunction "1_1") (pintype "passive"))
      (node (ref "SENSE") (pin "2") (pinfunction "2_2") (pintype "passive"))
      (node (ref "SJ2") (pin "2") (pinfunction "2_2") (pintype "passive"))
    )
    (net (code "77") (name "unconnected-(LED1-DO-Pad3)") (class "Default")
      (node (ref "LED1") (pin "3") (pinfunction "DO_3") (pintype "output"))
    )
    (net (code "78") (name "unconnected-(U$1A-PA15{slash}I15{slash}SERCOM2+4.3-Pad32)") (class "Default")
      (node (ref "U$1") (pin "32") (pinfunction "PA15/I15/SERCOM2+4.3_32") (pintype "bidirectional"))
    )
    (net (code "79") (name "unconnected-(U$1B-PB16{slash}I0{slash}SERCOM5.0{slash}I2SCK0-Pad39)") (class "Default")
      (node (ref "U$1") (pin "39") (pinfunction "PB16/I0/SERCOM5.0/I2SCK0_39") (pintype "bidirectional"))
    )
    (net (code "80") (name "unconnected-(U$1C-VSW-Pad55)") (class "Default")
      (node (ref "U$1") (pin "55") (pinfunction "VSW_55") (pintype "bidirectional"))
    )
    (net (code "81") (name "unconnected-(U1-B1-Pad18)") (class "Default")
      (node (ref "U1") (pin "18") (pinfunction "B1_18") (pintype "bidirectional"))
    )
    (net (code "82") (name "unconnected-(U1-B2-Pad17)") (class "Default")
      (node (ref "U1") (pin "17") (pinfunction "B2_17") (pintype "bidirectional"))
    )
    (net (code "83") (name "unconnected-(U2-NC{slash}FB-Pad4)") (class "Default")
      (node (ref "U2") (pin "4") (pinfunction "NC/FB_4") (pintype "passive"))
    )
    (net (code "84") (name "unconnected-(U4-INT2-Pad9)") (class "Default")
      (node (ref "U4") (pin "9") (pinfunction "INT2_9") (pintype "output"))
    )
    (net (code "85") (name "unconnected-(U4-NC-Pad2)") (class "Default")
      (node (ref "U4") (pin "2") (pinfunction "NC_2") (pintype "no_connect"))
    )
    (net (code "86") (name "unconnected-(U4-NC-Pad3)") (class "Default")
      (node (ref "U4") (pin "3") (pinfunction "NC_3") (pintype "no_connect"))
    )
    (net (code "87") (name "unconnected-(X5-SBU1-PadA8)") (class "Default")
      (node (ref "X5") (pin "A8") (pinfunction "SBU1_A8") (pintype "bidirectional"))
    )
    (net (code "88") (name "unconnected-(X5-SBU2-PadB8)") (class "Default")
      (node (ref "X5") (pin "B8") (pinfunction "SBU2_B8") (pintype "bidirectional"))
    )
    (net (code "89") (name "unconnected-(X6-CLK-Pad20)") (class "Default")
      (node (ref "X6") (pin "20") (pinfunction "CLK_20") (pintype "bidirectional"))
    )
    (net (code "90") (name "unconnected-(X6-CMD-Pad19)") (class "Default")
      (node (ref "X6") (pin "19") (pinfunction "CMD_19") (pintype "bidirectional"))
    )
    (net (code "91") (name "unconnected-(X6-I34{slash}A1_6-Pad6)") (class "Default")
      (node (ref "X6") (pin "6") (pinfunction "I34/A1_6_6") (pintype "bidirectional"))
    )
    (net (code "92") (name "unconnected-(X6-I35{slash}A1_7-Pad7)") (class "Default")
      (node (ref "X6") (pin "7") (pinfunction "I35/A1_7_7") (pintype "bidirectional"))
    )
    (net (code "93") (name "unconnected-(X6-IO2{slash}A2_2-Pad24)") (class "Default")
      (node (ref "X6") (pin "24") (pinfunction "IO2/A2_2_24") (pintype "bidirectional"))
    )
    (net (code "94") (name "unconnected-(X6-IO4{slash}A2_0-Pad26)") (class "Default")
      (node (ref "X6") (pin "26") (pinfunction "IO4/A2_0_26") (pintype "bidirectional"))
    )
    (net (code "95") (name "unconnected-(X6-IO12{slash}A2_5-Pad14)") (class "Default")
      (node (ref "X6") (pin "14") (pinfunction "IO12/A2_5_14") (pintype "bidirectional"))
    )
    (net (code "96") (name "unconnected-(X6-IO13{slash}A2_4-Pad16)") (class "Default")
      (node (ref "X6") (pin "16") (pinfunction "IO13/A2_4_16") (pintype "bidirectional"))
    )
    (net (code "97") (name "unconnected-(X6-IO15{slash}A2_3-Pad23)") (class "Default")
      (node (ref "X6") (pin "23") (pinfunction "IO15/A2_3_23") (pintype "bidirectional"))
    )
    (net (code "98") (name "unconnected-(X6-IO16-Pad27)") (class "Default")
      (node (ref "X6") (pin "27") (pinfunction "IO16_27") (pintype "bidirectional"))
    )
    (net (code "99") (name "unconnected-(X6-IO17-Pad28)") (class "Default")
      (node (ref "X6") (pin "28") (pinfunction "IO17_28") (pintype "bidirectional"))
    )
    (net (code "100") (name "unconnected-(X6-IO21-Pad33)") (class "Default")
      (node (ref "X6") (pin "33") (pinfunction "IO21_33") (pintype "bidirectional"))
    )
    (net (code "101") (name "unconnected-(X6-IO22-Pad36)") (class "Default")
      (node (ref "X6") (pin "36") (pinfunction "IO22_36") (pintype "bidirectional"))
    )
    (net (code "102") (name "unconnected-(X6-IO25{slash}DAC1{slash}A2_8-Pad10)") (class "Default")
      (node (ref "X6") (pin "10") (pinfunction "IO25/DAC1/A2_8_10") (pintype "bidirectional"))
    )
    (net (code "103") (name "unconnected-(X6-IO26{slash}DAC2{slash}A2_9-Pad11)") (class "Default")
      (node (ref "X6") (pin "11") (pinfunction "IO26/DAC2/A2_9_11") (pintype "bidirectional"))
    )
    (net (code "104") (name "unconnected-(X6-IO27{slash}A2_7-Pad12)") (class "Default")
      (node (ref "X6") (pin "12") (pinfunction "IO27/A2_7_12") (pintype "bidirectional"))
    )
    (net (code "105") (name "unconnected-(X6-IO32{slash}A1_4{slash}X32P-Pad8)") (class "Default")
      (node (ref "X6") (pin "8") (pinfunction "IO32/A1_4/X32P_8") (pintype "bidirectional"))
    )
    (net (code "106") (name "unconnected-(X6-IO36{slash}SEN_VP{slash}A1_0-Pad4)") (class "Default")
      (node (ref "X6") (pin "4") (pinfunction "IO36/SEN_VP/A1_0_4") (pintype "passive"))
    )
    (net (code "107") (name "unconnected-(X6-IO39{slash}SEN_VN{slash}A1_3-Pad5)") (class "Default")
      (node (ref "X6") (pin "5") (pinfunction "IO39/SEN_VN/A1_3_5") (pintype "passive"))
    )
    (net (code "108") (name "unconnected-(X6-SD0-Pad21)") (class "Default")
      (node (ref "X6") (pin "21") (pinfunction "SD0_21") (pintype "bidirectional"))
    )
    (net (code "109") (name "unconnected-(X6-SD1-Pad22)") (class "Default")
      (node (ref "X6") (pin "22") (pinfunction "SD1_22") (pintype "bidirectional"))
    )
    (net (code "110") (name "unconnected-(X6-SD2-Pad17)") (class "Default")
      (node (ref "X6") (pin "17") (pinfunction "SD2_17") (pintype "bidirectional"))
    )
    (net (code "111") (name "unconnected-(X6-SD3-Pad18)") (class "Default")
      (node (ref "X6") (pin "18") (pinfunction "SD3_18") (pintype "bidirectional"))
    )
  )
)
